# Sheet3.net
KiCad netlist of a schematic drawn in Altium Designer
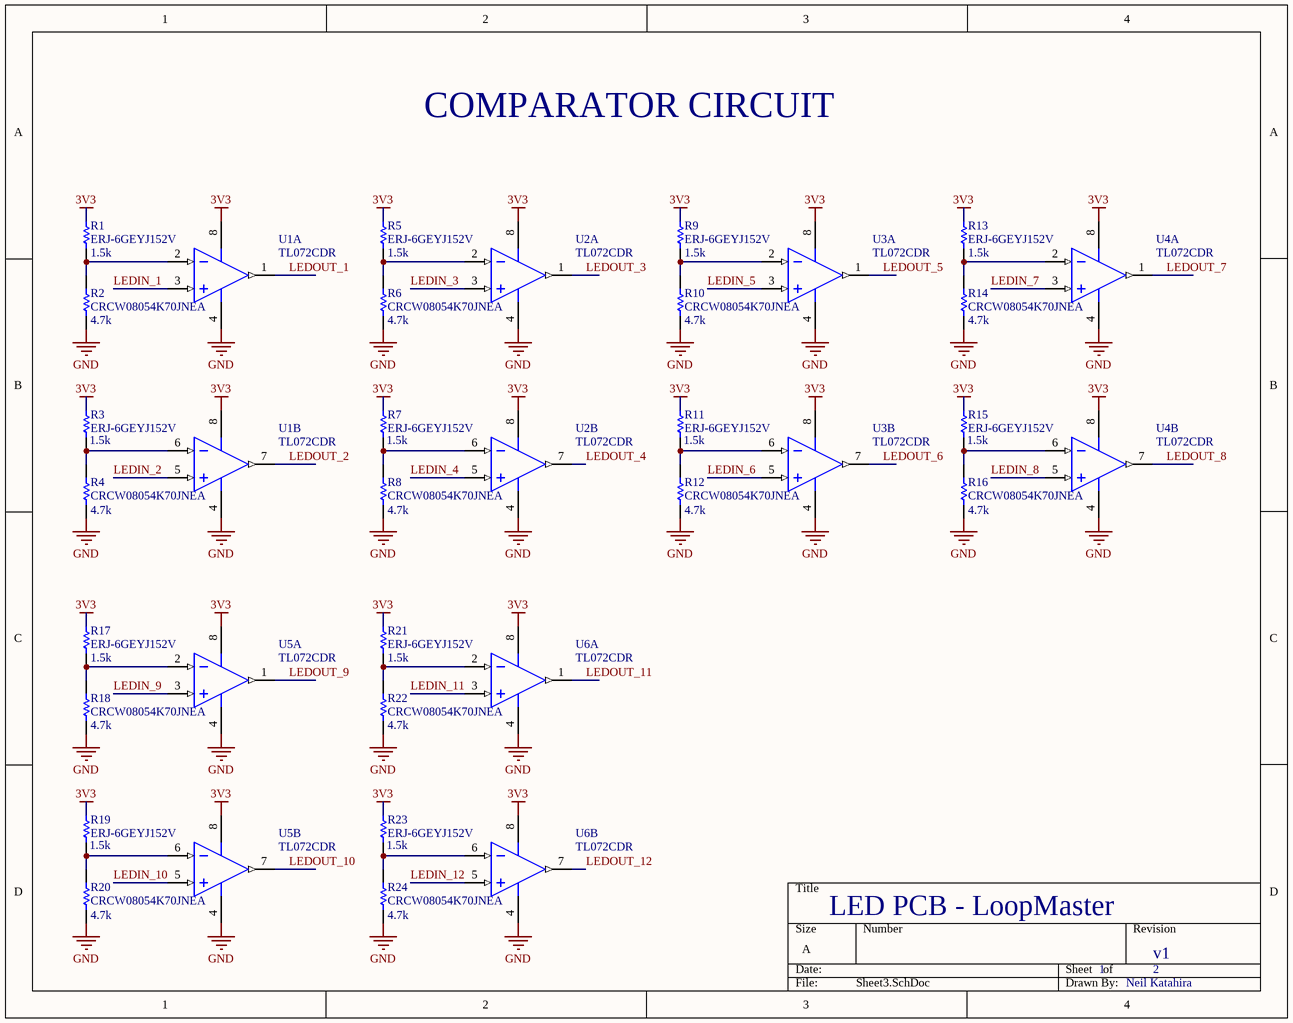
[diagram p0: Sheet3.SchDoc]

(export (version "E")
  (design (tool "Eeschema 10.0.6"))
  (components
    (comp (ref "R1")
      (value "ERJ-6GEYJ152V")
      (footprint "RESC2013X70X40NL20T20")
      (fields (field (name "MANUFACTURER") "Panasonic"))
      (libsource (lib "Altium Content Vault") (part "RES"))
    )
    (comp (ref "R2")
      (value "CRCW08054K70JNEA")
      (footprint "RESC2013X50X30LL20T20")
      (fields (field (name "MANUFACTURER") "Vishay Dale"))
      (libsource (lib "Altium Content Vault") (part "RES"))
    )
    (comp (ref "R3")
      (value "ERJ-6GEYJ152V")
      (footprint "RESC2013X70X40NL20T20")
      (fields (field (name "MANUFACTURER") "Panasonic"))
      (libsource (lib "Altium Content Vault") (part "RES"))
    )
    (comp (ref "R4")
      (value "CRCW08054K70JNEA")
      (footprint "RESC2013X50X30LL20T20")
      (fields (field (name "MANUFACTURER") "Vishay Dale"))
      (libsource (lib "Altium Content Vault") (part "RES"))
    )
    (comp (ref "R5")
      (value "ERJ-6GEYJ152V")
      (footprint "RESC2013X70X40NL20T20")
      (fields (field (name "MANUFACTURER") "Panasonic"))
      (libsource (lib "Altium Content Vault") (part "RES"))
    )
    (comp (ref "R6")
      (value "CRCW08054K70JNEA")
      (footprint "RESC2013X50X30LL20T20")
      (fields (field (name "MANUFACTURER") "Vishay Dale"))
      (libsource (lib "Altium Content Vault") (part "RES"))
    )
    (comp (ref "R7")
      (value "ERJ-6GEYJ152V")
      (footprint "RESC2013X70X40NL20T20")
      (fields (field (name "MANUFACTURER") "Panasonic"))
      (libsource (lib "Altium Content Vault") (part "RES"))
    )
    (comp (ref "R8")
      (value "CRCW08054K70JNEA")
      (footprint "RESC2013X50X30LL20T20")
      (fields (field (name "MANUFACTURER") "Vishay Dale"))
      (libsource (lib "Altium Content Vault") (part "RES"))
    )
    (comp (ref "R9")
      (value "ERJ-6GEYJ152V")
      (footprint "RESC2013X70X40NL20T20")
      (fields (field (name "MANUFACTURER") "Panasonic"))
      (libsource (lib "Altium Content Vault") (part "RES"))
    )
    (comp (ref "R10")
      (value "CRCW08054K70JNEA")
      (footprint "RESC2013X50X30LL20T20")
      (fields (field (name "MANUFACTURER") "Vishay Dale"))
      (libsource (lib "Altium Content Vault") (part "RES"))
    )
    (comp (ref "R11")
      (value "ERJ-6GEYJ152V")
      (footprint "RESC2013X70X40NL20T20")
      (fields (field (name "MANUFACTURER") "Panasonic"))
      (libsource (lib "Altium Content Vault") (part "RES"))
    )
    (comp (ref "R12")
      (value "CRCW08054K70JNEA")
      (footprint "RESC2013X50X30LL20T20")
      (fields (field (name "MANUFACTURER") "Vishay Dale"))
      (libsource (lib "Altium Content Vault") (part "RES"))
    )
    (comp (ref "R13")
      (value "ERJ-6GEYJ152V")
      (footprint "RESC2013X70X40NL20T20")
      (fields (field (name "MANUFACTURER") "Panasonic"))
      (libsource (lib "Altium Content Vault") (part "RES"))
    )
    (comp (ref "R14")
      (value "CRCW08054K70JNEA")
      (footprint "RESC2013X50X30LL20T20")
      (fields (field (name "MANUFACTURER") "Vishay Dale"))
      (libsource (lib "Altium Content Vault") (part "RES"))
    )
    (comp (ref "R15")
      (value "ERJ-6GEYJ152V")
      (footprint "RESC2013X70X40NL20T20")
      (fields (field (name "MANUFACTURER") "Panasonic"))
      (libsource (lib "Altium Content Vault") (part "RES"))
    )
    (comp (ref "R16")
      (value "CRCW08054K70JNEA")
      (footprint "RESC2013X50X30LL20T20")
      (fields (field (name "MANUFACTURER") "Vishay Dale"))
      (libsource (lib "Altium Content Vault") (part "RES"))
    )
    (comp (ref "R17")
      (value "ERJ-6GEYJ152V")
      (footprint "RESC2013X70X40NL20T20")
      (fields (field (name "MANUFACTURER") "Panasonic"))
      (libsource (lib "Altium Content Vault") (part "RES"))
    )
    (comp (ref "R18")
      (value "CRCW08054K70JNEA")
      (footprint "RESC2013X50X30LL20T20")
      (fields (field (name "MANUFACTURER") "Vishay Dale"))
      (libsource (lib "Altium Content Vault") (part "RES"))
    )
    (comp (ref "R19")
      (value "ERJ-6GEYJ152V")
      (footprint "RESC2013X70X40NL20T20")
      (fields (field (name "MANUFACTURER") "Panasonic"))
      (libsource (lib "Altium Content Vault") (part "RES"))
    )
    (comp (ref "R20")
      (value "CRCW08054K70JNEA")
      (footprint "RESC2013X50X30LL20T20")
      (fields (field (name "MANUFACTURER") "Vishay Dale"))
      (libsource (lib "Altium Content Vault") (part "RES"))
    )
    (comp (ref "R21")
      (value "ERJ-6GEYJ152V")
      (footprint "RESC2013X70X40NL20T20")
      (fields (field (name "MANUFACTURER") "Panasonic"))
      (libsource (lib "Altium Content Vault") (part "RES"))
    )
    (comp (ref "R22")
      (value "CRCW08054K70JNEA")
      (footprint "RESC2013X50X30LL20T20")
      (fields (field (name "MANUFACTURER") "Vishay Dale"))
      (libsource (lib "Altium Content Vault") (part "RES"))
    )
    (comp (ref "R23")
      (value "ERJ-6GEYJ152V")
      (footprint "RESC2013X70X40NL20T20")
      (fields (field (name "MANUFACTURER") "Panasonic"))
      (libsource (lib "Altium Content Vault") (part "RES"))
    )
    (comp (ref "R24")
      (value "CRCW08054K70JNEA")
      (footprint "RESC2013X50X30LL20T20")
      (fields (field (name "MANUFACTURER") "Vishay Dale"))
      (libsource (lib "Altium Content Vault") (part "RES"))
    )
    (comp (ref "U1")
      (value "TL072CDR")
      (footprint "D0008A_M")
      (fields (field (name "MANUFACTURER") "Texas Instruments"))
      (libsource (lib "Altium Content Vault") (part "TI-AMP-D6-2-8_D"))
    )
    (comp (ref "U2")
      (value "TL072CDR")
      (footprint "D0008A_M")
      (fields (field (name "MANUFACTURER") "Texas Instruments"))
      (libsource (lib "Altium Content Vault") (part "TI-AMP-D6-2-8_D"))
    )
    (comp (ref "U3")
      (value "TL072CDR")
      (footprint "D0008A_M")
      (fields (field (name "MANUFACTURER") "Texas Instruments"))
      (libsource (lib "Altium Content Vault") (part "TI-AMP-D6-2-8_D"))
    )
    (comp (ref "U4")
      (value "TL072CDR")
      (footprint "D0008A_M")
      (fields (field (name "MANUFACTURER") "Texas Instruments"))
      (libsource (lib "Altium Content Vault") (part "TI-AMP-D6-2-8_D"))
    )
    (comp (ref "U5")
      (value "TL072CDR")
      (footprint "D0008A_M")
      (fields (field (name "MANUFACTURER") "Texas Instruments"))
      (libsource (lib "Altium Content Vault") (part "TI-AMP-D6-2-8_D"))
    )
    (comp (ref "U6")
      (value "TL072CDR")
      (footprint "D0008A_M")
      (fields (field (name "MANUFACTURER") "Texas Instruments"))
      (libsource (lib "Altium Content Vault") (part "TI-AMP-D6-2-8_D"))
    )
  )
  (nets
    (net (code "1") (name "/LEDIN_1") (class "Default")
      (node (ref "U1") (pin "3") (pinfunction "IN1+_3") (pintype "input"))
    )
    (net (code "2") (name "/LEDIN_2") (class "Default")
      (node (ref "U1") (pin "5") (pinfunction "IN2+_5") (pintype "input"))
    )
    (net (code "3") (name "/LEDIN_3") (class "Default")
      (node (ref "U2") (pin "3") (pinfunction "IN1+_3") (pintype "input"))
    )
    (net (code "4") (name "/LEDIN_4") (class "Default")
      (node (ref "U2") (pin "5") (pinfunction "IN2+_5") (pintype "input"))
    )
    (net (code "5") (name "/LEDIN_5") (class "Default")
      (node (ref "U3") (pin "3") (pinfunction "IN1+_3") (pintype "input"))
    )
    (net (code "6") (name "/LEDIN_6") (class "Default")
      (node (ref "U3") (pin "5") (pinfunction "IN2+_5") (pintype "input"))
    )
    (net (code "7") (name "/LEDIN_7") (class "Default")
      (node (ref "U4") (pin "3") (pinfunction "IN1+_3") (pintype "input"))
    )
    (net (code "8") (name "/LEDIN_8") (class "Default")
      (node (ref "U4") (pin "5") (pinfunction "IN2+_5") (pintype "input"))
    )
    (net (code "9") (name "/LEDIN_9") (class "Default")
      (node (ref "U5") (pin "3") (pinfunction "IN1+_3") (pintype "input"))
    )
    (net (code "10") (name "/LEDIN_10") (class "Default")
      (node (ref "U5") (pin "5") (pinfunction "IN2+_5") (pintype "input"))
    )
    (net (code "11") (name "/LEDIN_11") (class "Default")
      (node (ref "U6") (pin "3") (pinfunction "IN1+_3") (pintype "input"))
    )
    (net (code "12") (name "/LEDIN_12") (class "Default")
      (node (ref "U6") (pin "5") (pinfunction "IN2+_5") (pintype "input"))
    )
    (net (code "13") (name "/LEDOUT_1") (class "Default")
      (node (ref "U1") (pin "1") (pinfunction "OUT1_1") (pintype "output"))
    )
    (net (code "14") (name "/LEDOUT_2") (class "Default")
      (node (ref "U1") (pin "7") (pinfunction "OUT2_7") (pintype "output"))
    )
    (net (code "15") (name "/LEDOUT_3") (class "Default")
      (node (ref "U2") (pin "1") (pinfunction "OUT1_1") (pintype "output"))
    )
    (net (code "16") (name "/LEDOUT_4") (class "Default")
      (node (ref "U2") (pin "7") (pinfunction "OUT2_7") (pintype "output"))
    )
    (net (code "17") (name "/LEDOUT_5") (class "Default")
      (node (ref "U3") (pin "1") (pinfunction "OUT1_1") (pintype "output"))
    )
    (net (code "18") (name "/LEDOUT_6") (class "Default")
      (node (ref "U3") (pin "7") (pinfunction "OUT2_7") (pintype "output"))
    )
    (net (code "19") (name "/LEDOUT_7") (class "Default")
      (node (ref "U4") (pin "1") (pinfunction "OUT1_1") (pintype "output"))
    )
    (net (code "20") (name "/LEDOUT_8") (class "Default")
      (node (ref "U4") (pin "7") (pinfunction "OUT2_7") (pintype "output"))
    )
    (net (code "21") (name "/LEDOUT_9") (class "Default")
      (node (ref "U5") (pin "1") (pinfunction "OUT1_1") (pintype "output"))
    )
    (net (code "22") (name "/LEDOUT_10") (class "Default")
      (node (ref "U5") (pin "7") (pinfunction "OUT2_7") (pintype "output"))
    )
    (net (code "23") (name "/LEDOUT_11") (class "Default")
      (node (ref "U6") (pin "1") (pinfunction "OUT1_1") (pintype "output"))
    )
    (net (code "24") (name "/LEDOUT_12") (class "Default")
      (node (ref "U6") (pin "7") (pinfunction "OUT2_7") (pintype "output"))
    )
    (net (code "25") (name "3V3") (class "Default")
      (node (ref "R1") (pin "2") (pinfunction "2_2") (pintype "passive"))
      (node (ref "R11") (pin "2") (pinfunction "2_2") (pintype "passive"))
      (node (ref "R13") (pin "2") (pinfunction "2_2") (pintype "passive"))
      (node (ref "R15") (pin "2") (pinfunction "2_2") (pintype "passive"))
      (node (ref "R17") (pin "2") (pinfunction "2_2") (pintype "passive"))
      (node (ref "R19") (pin "2") (pinfunction "2_2") (pintype "passive"))
      (node (ref "R21") (pin "2") (pinfunction "2_2") (pintype "passive"))
      (node (ref "R23") (pin "2") (pinfunction "2_2") (pintype "passive"))
      (node (ref "R3") (pin "2") (pinfunction "2_2") (pintype "passive"))
      (node (ref "R5") (pin "2") (pinfunction "2_2") (pintype "passive"))
      (node (ref "R7") (pin "2") (pinfunction "2_2") (pintype "passive"))
      (node (ref "R9") (pin "2") (pinfunction "2_2") (pintype "passive"))
      (node (ref "U1") (pin "8") (pinfunction "VCC+_8") (pintype "power_in"))
      (node (ref "U2") (pin "8") (pinfunction "VCC+_8") (pintype "power_in"))
      (node (ref "U3") (pin "8") (pinfunction "VCC+_8") (pintype "power_in"))
      (node (ref "U4") (pin "8") (pinfunction "VCC+_8") (pintype "power_in"))
      (node (ref "U5") (pin "8") (pinfunction "VCC+_8") (pintype "power_in"))
      (node (ref "U6") (pin "8") (pinfunction "VCC+_8") (pintype "power_in"))
    )
    (net (code "26") (name "GND") (class "Default")
      (node (ref "R10") (pin "1") (pinfunction "1_1") (pintype "passive"))
      (node (ref "R12") (pin "1") (pinfunction "1_1") (pintype "passive"))
      (node (ref "R14") (pin "1") (pinfunction "1_1") (pintype "passive"))
      (node (ref "R16") (pin "1") (pinfunction "1_1") (pintype "passive"))
      (node (ref "R18") (pin "1") (pinfunction "1_1") (pintype "passive"))
      (node (ref "R2") (pin "1") (pinfunction "1_1") (pintype "passive"))
      (node (ref "R20") (pin "1") (pinfunction "1_1") (pintype "passive"))
      (node (ref "R22") (pin "1") (pinfunction "1_1") (pintype "passive"))
      (node (ref "R24") (pin "1") (pinfunction "1_1") (pintype "passive"))
      (node (ref "R4") (pin "1") (pinfunction "1_1") (pintype "passive"))
      (node (ref "R6") (pin "1") (pinfunction "1_1") (pintype "passive"))
      (node (ref "R8") (pin "1") (pinfunction "1_1") (pintype "passive"))
      (node (ref "U1") (pin "4") (pinfunction "VCC-_4") (pintype "power_in"))
      (node (ref "U2") (pin "4") (pinfunction "VCC-_4") (pintype "power_in"))
      (node (ref "U3") (pin "4") (pinfunction "VCC-_4") (pintype "power_in"))
      (node (ref "U4") (pin "4") (pinfunction "VCC-_4") (pintype "power_in"))
      (node (ref "U5") (pin "4") (pinfunction "VCC-_4") (pintype "power_in"))
      (node (ref "U6") (pin "4") (pinfunction "VCC-_4") (pintype "power_in"))
    )
    (net (code "27") (name "Net-(U1A-IN1-)") (class "Default")
      (node (ref "R1") (pin "1") (pinfunction "1_1") (pintype "passive"))
      (node (ref "R2") (pin "2") (pinfunction "2_2") (pintype "passive"))
      (node (ref "U1") (pin "2") (pinfunction "IN1-_2") (pintype "input"))
    )
    (net (code "28") (name "Net-(U1B-IN2-)") (class "Default")
      (node (ref "R3") (pin "1") (pinfunction "1_1") (pintype "passive"))
      (node (ref "R4") (pin "2") (pinfunction "2_2") (pintype "passive"))
      (node (ref "U1") (pin "6") (pinfunction "IN2-_6") (pintype "input"))
    )
    (net (code "29") (name "Net-(U2A-IN1-)") (class "Default")
      (node (ref "R5") (pin "1") (pinfunction "1_1") (pintype "passive"))
      (node (ref "R6") (pin "2") (pinfunction "2_2") (pintype "passive"))
      (node (ref "U2") (pin "2") (pinfunction "IN1-_2") (pintype "input"))
    )
    (net (code "30") (name "Net-(U2B-IN2-)") (class "Default")
      (node (ref "R7") (pin "1") (pinfunction "1_1") (pintype "passive"))
      (node (ref "R8") (pin "2") (pinfunction "2_2") (pintype "passive"))
      (node (ref "U2") (pin "6") (pinfunction "IN2-_6") (pintype "input"))
    )
    (net (code "31") (name "Net-(U3A-IN1-)") (class "Default")
      (node (ref "R10") (pin "2") (pinfunction "2_2") (pintype "passive"))
      (node (ref "R9") (pin "1") (pinfunction "1_1") (pintype "passive"))
      (node (ref "U3") (pin "2") (pinfunction "IN1-_2") (pintype "input"))
    )
    (net (code "32") (name "Net-(U3B-IN2-)") (class "Default")
      (node (ref "R11") (pin "1") (pinfunction "1_1") (pintype "passive"))
      (node (ref "R12") (pin "2") (pinfunction "2_2") (pintype "passive"))
      (node (ref "U3") (pin "6") (pinfunction "IN2-_6") (pintype "input"))
    )
    (net (code "33") (name "Net-(U4A-IN1-)") (class "Default")
      (node (ref "R13") (pin "1") (pinfunction "1_1") (pintype "passive"))
      (node (ref "R14") (pin "2") (pinfunction "2_2") (pintype "passive"))
      (node (ref "U4") (pin "2") (pinfunction "IN1-_2") (pintype "input"))
    )
    (net (code "34") (name "Net-(U4B-IN2-)") (class "Default")
      (node (ref "R15") (pin "1") (pinfunction "1_1") (pintype "passive"))
      (node (ref "R16") (pin "2") (pinfunction "2_2") (pintype "passive"))
      (node (ref "U4") (pin "6") (pinfunction "IN2-_6") (pintype "input"))
    )
    (net (code "35") (name "Net-(U5A-IN1-)") (class "Default")
      (node (ref "R17") (pin "1") (pinfunction "1_1") (pintype "passive"))
      (node (ref "R18") (pin "2") (pinfunction "2_2") (pintype "passive"))
      (node (ref "U5") (pin "2") (pinfunction "IN1-_2") (pintype "input"))
    )
    (net (code "36") (name "Net-(U5B-IN2-)") (class "Default")
      (node (ref "R19") (pin "1") (pinfunction "1_1") (pintype "passive"))
      (node (ref "R20") (pin "2") (pinfunction "2_2") (pintype "passive"))
      (node (ref "U5") (pin "6") (pinfunction "IN2-_6") (pintype "input"))
    )
    (net (code "37") (name "Net-(U6A-IN1-)") (class "Default")
      (node (ref "R21") (pin "1") (pinfunction "1_1") (pintype "passive"))
      (node (ref "R22") (pin "2") (pinfunction "2_2") (pintype "passive"))
      (node (ref "U6") (pin "2") (pinfunction "IN1-_2") (pintype "input"))
    )
    (net (code "38") (name "Net-(U6B-IN2-)") (class "Default")
      (node (ref "R23") (pin "1") (pinfunction "1_1") (pintype "passive"))
      (node (ref "R24") (pin "2") (pinfunction "2_2") (pintype "passive"))
      (node (ref "U6") (pin "6") (pinfunction "IN2-_6") (pintype "input"))
    )
  )
)
